# Pressure_Transducers.net
KiCad netlist of a schematic drawn in Altium Designer
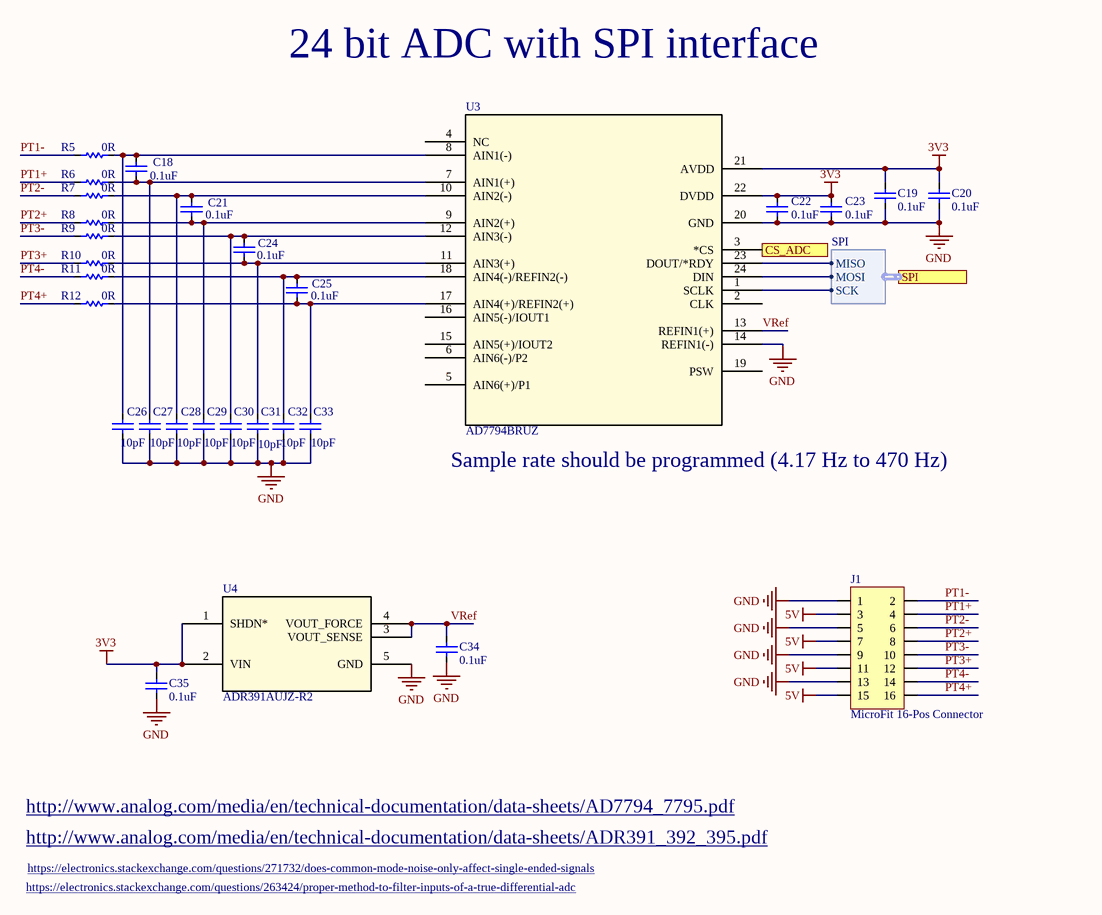
[diagram p0: Pressure_Transducers.SchDoc]

(export (version "E")
  (design (tool "Eeschema 10.0.6"))
  (components
    (comp (ref "C18")
      (value "0.1uF")
      (footprint "0603")
      (fields (field (name "Comment") "Cap"))
      (libsource (lib "RPL_POWER") (part "Cap"))
    )
    (comp (ref "C19")
      (value "0.1uF")
      (footprint "0603")
      (fields (field (name "Comment") "Cap"))
      (libsource (lib "RPL_POWER") (part "Cap"))
    )
    (comp (ref "C20")
      (value "0.1uF")
      (footprint "0603")
      (fields (field (name "Comment") "Cap"))
      (libsource (lib "RPL_POWER") (part "Cap"))
    )
    (comp (ref "C21")
      (value "0.1uF")
      (footprint "0603")
      (fields (field (name "Comment") "Cap"))
      (libsource (lib "RPL_POWER") (part "Cap"))
    )
    (comp (ref "C22")
      (value "0.1uF")
      (footprint "0603")
      (fields (field (name "Comment") "Cap"))
      (libsource (lib "RPL_POWER") (part "Cap"))
    )
    (comp (ref "C23")
      (value "0.1uF")
      (footprint "0603")
      (fields (field (name "Comment") "Cap"))
      (libsource (lib "RPL_POWER") (part "Cap"))
    )
    (comp (ref "C24")
      (value "0.1uF")
      (footprint "0603")
      (fields (field (name "Comment") "Cap"))
      (libsource (lib "RPL_POWER") (part "Cap"))
    )
    (comp (ref "C25")
      (value "0.1uF")
      (footprint "0603")
      (fields (field (name "Comment") "Cap"))
      (libsource (lib "RPL_POWER") (part "Cap"))
    )
    (comp (ref "C26")
      (value "10pF")
      (footprint "0603")
      (fields (field (name "Comment") "Cap"))
      (libsource (lib "RPL_POWER") (part "Cap"))
    )
    (comp (ref "C27")
      (value "10pF")
      (footprint "0603")
      (fields (field (name "Comment") "Cap"))
      (libsource (lib "RPL_POWER") (part "Cap"))
    )
    (comp (ref "C28")
      (value "10pF")
      (footprint "0603")
      (fields (field (name "Comment") "Cap"))
      (libsource (lib "RPL_POWER") (part "Cap"))
    )
    (comp (ref "C29")
      (value "10pF")
      (footprint "0603")
      (fields (field (name "Comment") "Cap"))
      (libsource (lib "RPL_POWER") (part "Cap"))
    )
    (comp (ref "C30")
      (value "10pF")
      (footprint "0603")
      (fields (field (name "Comment") "Cap"))
      (libsource (lib "RPL_POWER") (part "Cap"))
    )
    (comp (ref "C31")
      (value "10pF")
      (footprint "0603")
      (fields (field (name "Comment") "Cap"))
      (libsource (lib "RPL_POWER") (part "Cap"))
    )
    (comp (ref "C32")
      (value "10pF")
      (footprint "0603")
      (fields (field (name "Comment") "Cap"))
      (libsource (lib "RPL_POWER") (part "Cap"))
    )
    (comp (ref "C33")
      (value "10pF")
      (footprint "0603")
      (fields (field (name "Comment") "Cap"))
      (libsource (lib "RPL_POWER") (part "Cap"))
    )
    (comp (ref "C34")
      (value "0.1uF")
      (footprint "0603")
      (fields (field (name "Comment") "Cap"))
      (libsource (lib "RPL_POWER") (part "Cap"))
    )
    (comp (ref "C35")
      (value "0.1uF")
      (footprint "0603")
      (fields (field (name "Comment") "Cap"))
      (libsource (lib "RPL_POWER") (part "Cap"))
    )
    (comp (ref "J1")
      (value "MicroFit 16-Pos Connector")
      (footprint "Microfit-16Pos")
      (description "Molex MicroFit 16-Pos Connector")
      (libsource (lib "LaunchyRIOComponents") (part "Micro-Fit 16Pos"))
    )
    (comp (ref "R5")
      (value "0R")
      (footprint "SB-2pos")
      (fields (field (name "Comment") "Res"))
      (libsource (lib "RPL_POWER") (part "Res"))
    )
    (comp (ref "R6")
      (value "0R")
      (footprint "SB-2pos")
      (fields (field (name "Comment") "Res"))
      (libsource (lib "RPL_POWER") (part "Res"))
    )
    (comp (ref "R7")
      (value "0R")
      (footprint "SB-2pos")
      (fields (field (name "Comment") "Res"))
      (libsource (lib "RPL_POWER") (part "Res"))
    )
    (comp (ref "R8")
      (value "0R")
      (footprint "SB-2pos")
      (fields (field (name "Comment") "Res"))
      (libsource (lib "RPL_POWER") (part "Res"))
    )
    (comp (ref "R9")
      (value "0R")
      (footprint "SB-2pos")
      (fields (field (name "Comment") "Res"))
      (libsource (lib "RPL_POWER") (part "Res"))
    )
    (comp (ref "R10")
      (value "0R")
      (footprint "SB-2pos")
      (fields (field (name "Comment") "Res"))
      (libsource (lib "RPL_POWER") (part "Res"))
    )
    (comp (ref "R11")
      (value "0R")
      (footprint "SB-2pos")
      (fields (field (name "Comment") "Res"))
      (libsource (lib "RPL_POWER") (part "Res"))
    )
    (comp (ref "R12")
      (value "0R")
      (footprint "SB-2pos")
      (fields (field (name "Comment") "Res"))
      (libsource (lib "RPL_POWER") (part "Res"))
    )
    (comp (ref "U3")
      (value "AD7794BRUZ")
      (footprint "RU_24")
      (description "Imported")
      (libsource (lib "LaunchyRIOComponents") (part "AD7794BRUZ"))
    )
    (comp (ref "U4")
      (value "ADR391AUJZ-R2")
      (footprint "UJ_5")
      (description "Imported")
      (libsource (lib "LaunchyRIOComponents") (part "ADR391AUJZ-R2"))
    )
  )
  (nets
    (net (code "2") (name "/CS_ADC") (class "Default")
      (node (ref "U3") (pin "3") (pinfunction "*CS_3") (pintype "passive"))
    )
    (net (code "3") (name "/MISO") (class "Default")
      (node (ref "U3") (pin "23") (pinfunction "DOUT/*RDY_23") (pintype "passive"))
    )
    (net (code "4") (name "/MOSI") (class "Default")
      (node (ref "U3") (pin "24") (pinfunction "DIN_24") (pintype "passive"))
    )
    (net (code "5") (name "/PT1+") (class "Default")
      (node (ref "J1") (pin "4") (pinfunction "4_4") (pintype "passive"))
      (node (ref "R6") (pin "1") (pinfunction "1_1") (pintype "passive"))
    )
    (net (code "6") (name "/PT1-") (class "Default")
      (node (ref "J1") (pin "2") (pinfunction "2_2") (pintype "passive"))
      (node (ref "R5") (pin "1") (pinfunction "1_1") (pintype "passive"))
    )
    (net (code "7") (name "/PT2+") (class "Default")
      (node (ref "J1") (pin "8") (pinfunction "8_8") (pintype "passive"))
      (node (ref "R8") (pin "1") (pinfunction "1_1") (pintype "passive"))
    )
    (net (code "8") (name "/PT2-") (class "Default")
      (node (ref "J1") (pin "6") (pinfunction "6_6") (pintype "passive"))
      (node (ref "R7") (pin "1") (pinfunction "1_1") (pintype "passive"))
    )
    (net (code "9") (name "/PT3+") (class "Default")
      (node (ref "J1") (pin "12") (pinfunction "12_12") (pintype "passive"))
      (node (ref "R10") (pin "1") (pinfunction "1_1") (pintype "passive"))
    )
    (net (code "10") (name "/PT3-") (class "Default")
      (node (ref "J1") (pin "10") (pinfunction "10_10") (pintype "passive"))
      (node (ref "R9") (pin "1") (pinfunction "1_1") (pintype "passive"))
    )
    (net (code "11") (name "/PT4+") (class "Default")
      (node (ref "J1") (pin "16") (pinfunction "16_16") (pintype "passive"))
      (node (ref "R12") (pin "1") (pinfunction "1_1") (pintype "passive"))
    )
    (net (code "12") (name "/PT4-") (class "Default")
      (node (ref "J1") (pin "14") (pinfunction "14_14") (pintype "passive"))
      (node (ref "R11") (pin "1") (pinfunction "1_1") (pintype "passive"))
    )
    (net (code "13") (name "/SCK") (class "Default")
      (node (ref "U3") (pin "1") (pinfunction "SCLK_1") (pintype "passive"))
    )
    (net (code "14") (name "/VRef") (class "Default")
      (node (ref "C34") (pin "2") (pinfunction "2_2") (pintype "passive"))
      (node (ref "U3") (pin "13") (pinfunction "REFIN1(+)_13") (pintype "passive"))
      (node (ref "U4") (pin "3") (pinfunction "VOUT_SENSE_3") (pintype "passive"))
      (node (ref "U4") (pin "4") (pinfunction "VOUT_FORCE_4") (pintype "passive"))
    )
    (net (code "16") (name "3V3") (class "Default")
      (node (ref "C19") (pin "2") (pinfunction "2_2") (pintype "passive"))
      (node (ref "C20") (pin "2") (pinfunction "2_2") (pintype "passive"))
      (node (ref "C22") (pin "2") (pinfunction "2_2") (pintype "passive"))
      (node (ref "C23") (pin "2") (pinfunction "2_2") (pintype "passive"))
      (node (ref "C35") (pin "2") (pinfunction "2_2") (pintype "passive"))
      (node (ref "U3") (pin "21") (pinfunction "AVDD_21") (pintype "passive"))
      (node (ref "U3") (pin "22") (pinfunction "DVDD_22") (pintype "passive"))
      (node (ref "U4") (pin "1") (pinfunction "SHDN*_1") (pintype "passive"))
      (node (ref "U4") (pin "2") (pinfunction "VIN_2") (pintype "passive"))
    )
    (net (code "17") (name "5V") (class "Default")
      (node (ref "J1") (pin "11") (pinfunction "11_11") (pintype "passive"))
      (node (ref "J1") (pin "15") (pinfunction "15_15") (pintype "passive"))
      (node (ref "J1") (pin "3") (pinfunction "3_3") (pintype "passive"))
      (node (ref "J1") (pin "7") (pinfunction "7_7") (pintype "passive"))
    )
    (net (code "18") (name "GND") (class "Default")
      (node (ref "C19") (pin "1") (pinfunction "1_1") (pintype "passive"))
      (node (ref "C20") (pin "1") (pinfunction "1_1") (pintype "passive"))
      (node (ref "C22") (pin "1") (pinfunction "1_1") (pintype "passive"))
      (node (ref "C23") (pin "1") (pinfunction "1_1") (pintype "passive"))
      (node (ref "C26") (pin "1") (pinfunction "1_1") (pintype "passive"))
      (node (ref "C27") (pin "1") (pinfunction "1_1") (pintype "passive"))
      (node (ref "C28") (pin "1") (pinfunction "1_1") (pintype "passive"))
      (node (ref "C29") (pin "1") (pinfunction "1_1") (pintype "passive"))
      (node (ref "C30") (pin "1") (pinfunction "1_1") (pintype "passive"))
      (node (ref "C31") (pin "1") (pinfunction "1_1") (pintype "passive"))
      (node (ref "C32") (pin "1") (pinfunction "1_1") (pintype "passive"))
      (node (ref "C33") (pin "1") (pinfunction "1_1") (pintype "passive"))
      (node (ref "C34") (pin "1") (pinfunction "1_1") (pintype "passive"))
      (node (ref "C35") (pin "1") (pinfunction "1_1") (pintype "passive"))
      (node (ref "J1") (pin "1") (pinfunction "1_1") (pintype "passive"))
      (node (ref "J1") (pin "13") (pinfunction "13_13") (pintype "passive"))
      (node (ref "J1") (pin "5") (pinfunction "5_5") (pintype "passive"))
      (node (ref "J1") (pin "9") (pinfunction "9_9") (pintype "passive"))
      (node (ref "U3") (pin "14") (pinfunction "REFIN1(-)_14") (pintype "passive"))
      (node (ref "U3") (pin "20") (pinfunction "GND_20") (pintype "passive"))
      (node (ref "U4") (pin "5") (pinfunction "GND_5") (pintype "passive"))
    )
    (net (code "19") (name "Net-(U3-AIN1(+))") (class "Default")
      (node (ref "C18") (pin "1") (pinfunction "1_1") (pintype "passive"))
      (node (ref "C27") (pin "2") (pinfunction "2_2") (pintype "passive"))
      (node (ref "R6") (pin "2") (pinfunction "2_2") (pintype "passive"))
      (node (ref "U3") (pin "7") (pinfunction "AIN1(+)_7") (pintype "passive"))
    )
    (net (code "20") (name "Net-(U3-AIN1(-))") (class "Default")
      (node (ref "C18") (pin "2") (pinfunction "2_2") (pintype "passive"))
      (node (ref "C26") (pin "2") (pinfunction "2_2") (pintype "passive"))
      (node (ref "R5") (pin "2") (pinfunction "2_2") (pintype "passive"))
      (node (ref "U3") (pin "8") (pinfunction "AIN1(-)_8") (pintype "passive"))
    )
    (net (code "21") (name "Net-(U3-AIN2(+))") (class "Default")
      (node (ref "C21") (pin "1") (pinfunction "1_1") (pintype "passive"))
      (node (ref "C29") (pin "2") (pinfunction "2_2") (pintype "passive"))
      (node (ref "R8") (pin "2") (pinfunction "2_2") (pintype "passive"))
      (node (ref "U3") (pin "9") (pinfunction "AIN2(+)_9") (pintype "passive"))
    )
    (net (code "22") (name "Net-(U3-AIN2(-))") (class "Default")
      (node (ref "C21") (pin "2") (pinfunction "2_2") (pintype "passive"))
      (node (ref "C28") (pin "2") (pinfunction "2_2") (pintype "passive"))
      (node (ref "R7") (pin "2") (pinfunction "2_2") (pintype "passive"))
      (node (ref "U3") (pin "10") (pinfunction "AIN2(-)_10") (pintype "passive"))
    )
    (net (code "23") (name "Net-(U3-AIN3(+))") (class "Default")
      (node (ref "C24") (pin "1") (pinfunction "1_1") (pintype "passive"))
      (node (ref "C31") (pin "2") (pinfunction "2_2") (pintype "passive"))
      (node (ref "R10") (pin "2") (pinfunction "2_2") (pintype "passive"))
      (node (ref "U3") (pin "11") (pinfunction "AIN3(+)_11") (pintype "passive"))
    )
    (net (code "24") (name "Net-(U3-AIN3(-))") (class "Default")
      (node (ref "C24") (pin "2") (pinfunction "2_2") (pintype "passive"))
      (node (ref "C30") (pin "2") (pinfunction "2_2") (pintype "passive"))
      (node (ref "R9") (pin "2") (pinfunction "2_2") (pintype "passive"))
      (node (ref "U3") (pin "12") (pinfunction "AIN3(-)_12") (pintype "passive"))
    )
    (net (code "25") (name "Net-(U3-AIN4(+){slash}REFIN2(+))") (class "Default")
      (node (ref "C25") (pin "1") (pinfunction "1_1") (pintype "passive"))
      (node (ref "C33") (pin "2") (pinfunction "2_2") (pintype "passive"))
      (node (ref "R12") (pin "2") (pinfunction "2_2") (pintype "passive"))
      (node (ref "U3") (pin "17") (pinfunction "AIN4(+)/REFIN2(+)_17") (pintype "passive"))
    )
    (net (code "26") (name "Net-(U3-AIN4(-){slash}REFIN2(-))") (class "Default")
      (node (ref "C25") (pin "2") (pinfunction "2_2") (pintype "passive"))
      (node (ref "C32") (pin "2") (pinfunction "2_2") (pintype "passive"))
      (node (ref "R11") (pin "2") (pinfunction "2_2") (pintype "passive"))
      (node (ref "U3") (pin "18") (pinfunction "AIN4(-)/REFIN2(-)_18") (pintype "passive"))
    )
    (net (code "27") (name "unconnected-(U3-AIN5(+){slash}IOUT2-Pad15)") (class "Default")
      (node (ref "U3") (pin "15") (pinfunction "AIN5(+)/IOUT2_15") (pintype "passive"))
    )
    (net (code "28") (name "unconnected-(U3-AIN5(-){slash}IOUT1-Pad16)") (class "Default")
      (node (ref "U3") (pin "16") (pinfunction "AIN5(-)/IOUT1_16") (pintype "passive"))
    )
    (net (code "29") (name "unconnected-(U3-AIN6(+){slash}P1-Pad5)") (class "Default")
      (node (ref "U3") (pin "5") (pinfunction "AIN6(+)/P1_5") (pintype "passive"))
    )
    (net (code "30") (name "unconnected-(U3-AIN6(-){slash}P2-Pad6)") (class "Default")
      (node (ref "U3") (pin "6") (pinfunction "AIN6(-)/P2_6") (pintype "passive"))
    )
    (net (code "31") (name "unconnected-(U3-CLK-Pad2)") (class "Default")
      (node (ref "U3") (pin "2") (pinfunction "CLK_2") (pintype "passive"))
    )
    (net (code "32") (name "unconnected-(U3-NC-Pad4)") (class "Default")
      (node (ref "U3") (pin "4") (pinfunction "NC_4") (pintype "passive"))
    )
    (net (code "33") (name "unconnected-(U3-PSW-Pad19)") (class "Default")
      (node (ref "U3") (pin "19") (pinfunction "PSW_19") (pintype "passive"))
    )
  )
)
